# Rechargeable_battery_capacity_tester.net
KiCad netlist of a schematic drawn in EAGLE
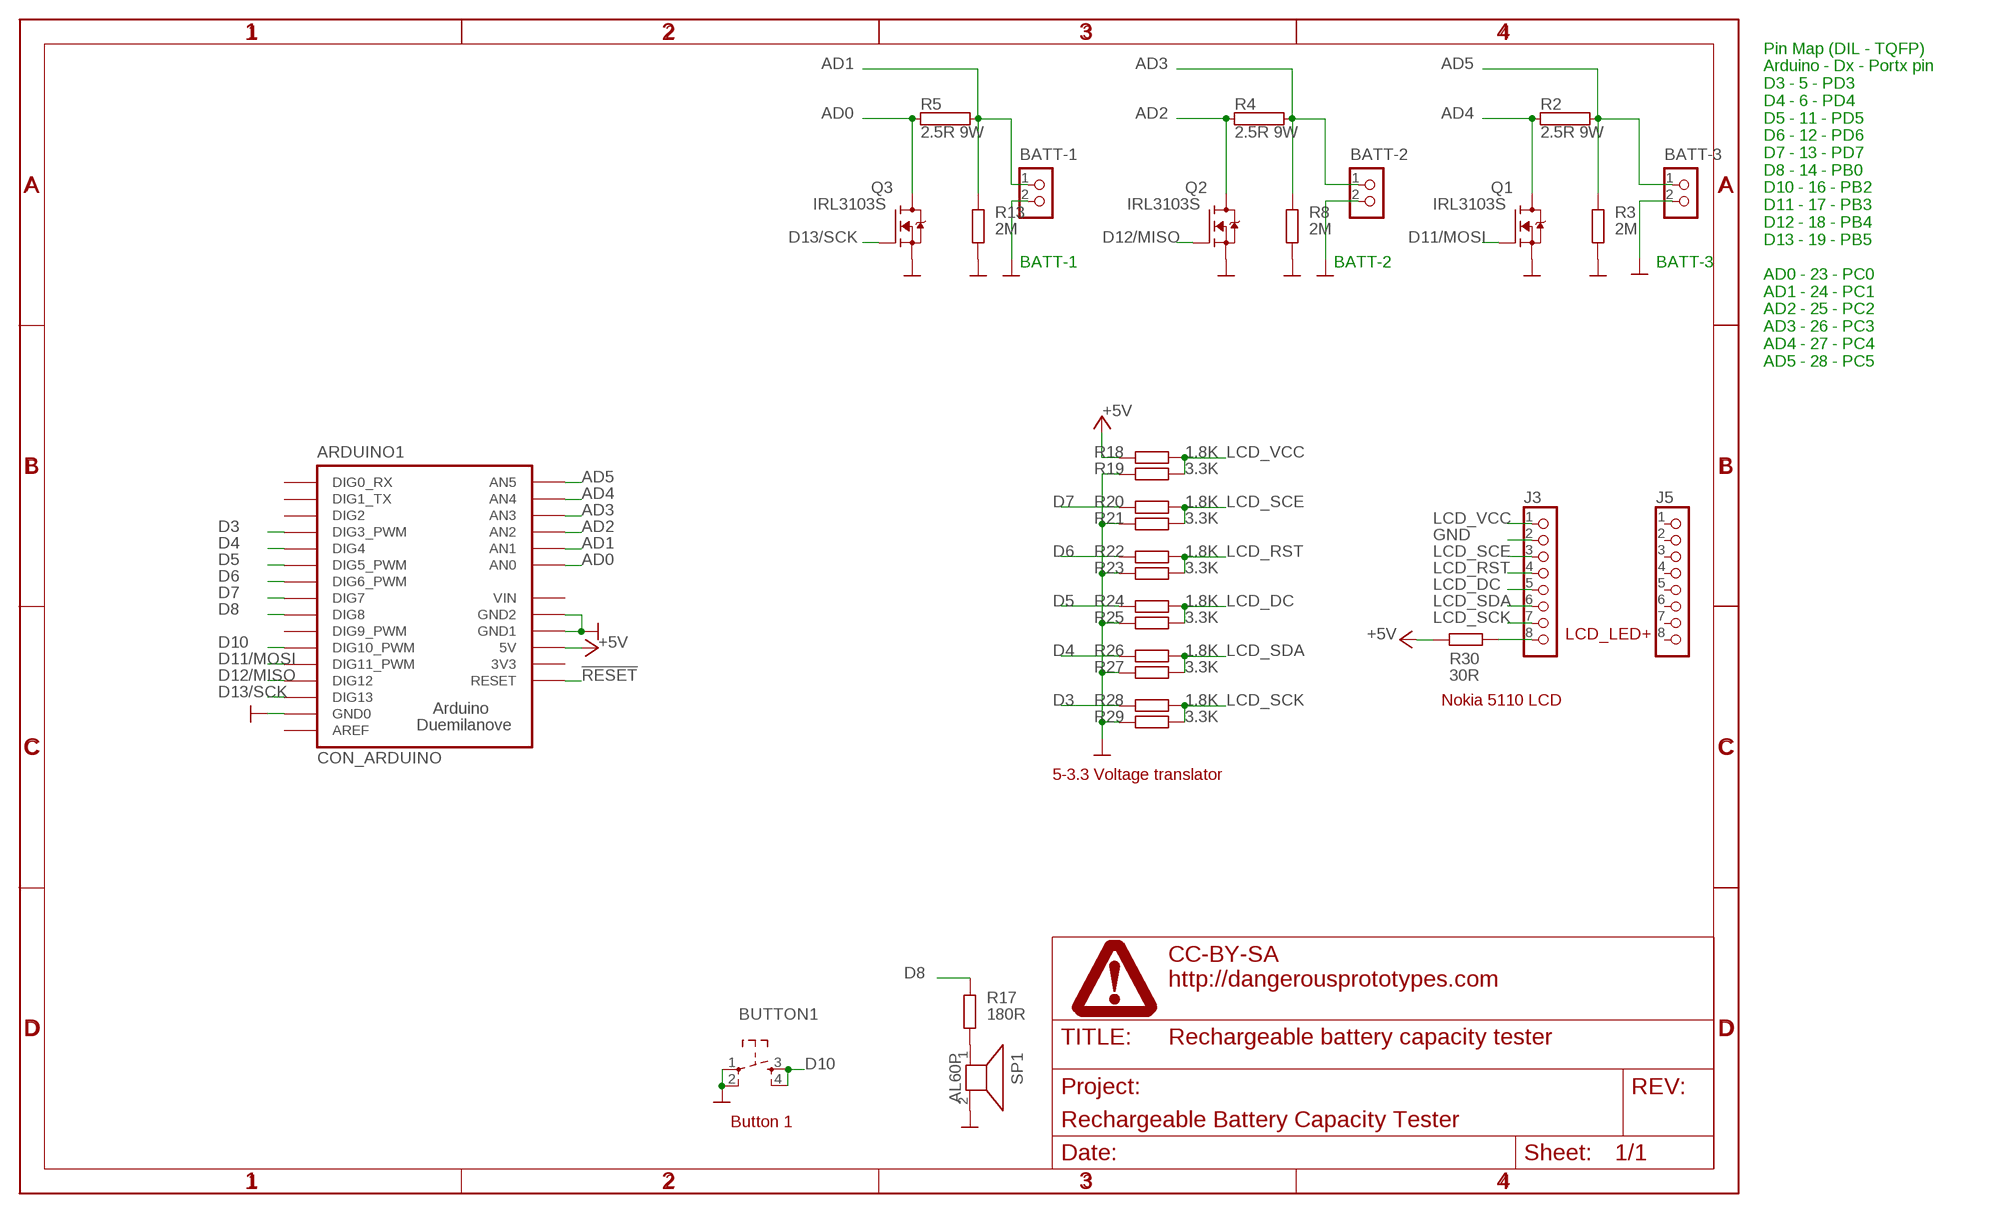
[diagram p0: schematic, sheet 1]

(export (version "E")
  (design (tool "Eeschema 10.0.6"))
  (components
    (comp (ref "ARDUINO1")
      (value "CON_ARDUINO")
      (footprint "eagle-import:CON_ARDUINO")
      (libsource (lib "eagle-import") (part "CON_ARDUINO"))
    )
    (comp (ref "BATT-1")
      (value "CON_TERMINAL_BLOCK_02-5MM")
      (footprint "eagle-import:TERMINAL_BLOCK_2P_5")
      (libsource (lib "eagle-import") (part "CON_TERMINAL_BLOCK_02-5MM"))
    )
    (comp (ref "BATT-2")
      (value "CON_TERMINAL_BLOCK_02-5MM")
      (footprint "eagle-import:TERMINAL_BLOCK_2P_5")
      (libsource (lib "eagle-import") (part "CON_TERMINAL_BLOCK_02-5MM"))
    )
    (comp (ref "BATT-3")
      (value "CON_TERMINAL_BLOCK_02-5MM")
      (footprint "eagle-import:TERMINAL_BLOCK_2P_5")
      (libsource (lib "eagle-import") (part "CON_TERMINAL_BLOCK_02-5MM"))
    )
    (comp (ref "BUTTON1")
      (value "SW_TACT_4P")
      (footprint "eagle-import:SW_TACT_SMALL")
      (libsource (lib "eagle-import") (part "SW_TACT_4P"))
    )
    (comp (ref "J3")
      (value "CON_HEADER_1X08-PTH")
      (footprint "eagle-import:M1X8")
      (libsource (lib "eagle-import") (part "CON_HEADER_1X08-PTH"))
    )
    (comp (ref "J5")
      (value "CON_HEADER_1X08-PTH")
      (footprint "eagle-import:M1X8")
      (libsource (lib "eagle-import") (part "CON_HEADER_1X08-PTH"))
    )
    (comp (ref "Q1")
      (value "IRL3103S")
      (footprint "eagle-import:D2PAK")
      (libsource (lib "eagle-import") (part "TRANSISTOR_MOSFET-N-D2PAK"))
    )
    (comp (ref "Q2")
      (value "IRL3103S")
      (footprint "eagle-import:D2PAK")
      (libsource (lib "eagle-import") (part "TRANSISTOR_MOSFET-N-D2PAK"))
    )
    (comp (ref "Q3")
      (value "IRL3103S")
      (footprint "eagle-import:D2PAK")
      (libsource (lib "eagle-import") (part "TRANSISTOR_MOSFET-N-D2PAK"))
    )
    (comp (ref "R2")
      (value "2.5R 9W")
      (footprint "eagle-import:KH208-8")
      (libsource (lib "eagle-import") (part "RKH208-8"))
    )
    (comp (ref "R3")
      (value "2M")
      (footprint "eagle-import:R603")
      (libsource (lib "eagle-import") (part "RESISTOR-0603"))
    )
    (comp (ref "R4")
      (value "2.5R 9W")
      (footprint "eagle-import:KH208-8")
      (libsource (lib "eagle-import") (part "RKH208-8"))
    )
    (comp (ref "R5")
      (value "2.5R 9W")
      (footprint "eagle-import:KH208-8")
      (libsource (lib "eagle-import") (part "RKH208-8"))
    )
    (comp (ref "R8")
      (value "2M")
      (footprint "eagle-import:R603")
      (libsource (lib "eagle-import") (part "RESISTOR-0603"))
    )
    (comp (ref "R13")
      (value "2M")
      (footprint "eagle-import:R603")
      (libsource (lib "eagle-import") (part "RESISTOR-0603"))
    )
    (comp (ref "R17")
      (value "180R")
      (footprint "eagle-import:R603")
      (libsource (lib "eagle-import") (part "RESISTOR-0603"))
    )
    (comp (ref "R18")
      (value "1.8K")
      (footprint "eagle-import:R603")
      (libsource (lib "eagle-import") (part "RESISTOR-0603"))
    )
    (comp (ref "R19")
      (value "3.3K")
      (footprint "eagle-import:R603")
      (libsource (lib "eagle-import") (part "RESISTOR-0603"))
    )
    (comp (ref "R20")
      (value "1.8K")
      (footprint "eagle-import:R603")
      (libsource (lib "eagle-import") (part "RESISTOR-0603"))
    )
    (comp (ref "R21")
      (value "3.3K")
      (footprint "eagle-import:R603")
      (libsource (lib "eagle-import") (part "RESISTOR-0603"))
    )
    (comp (ref "R22")
      (value "1.8K")
      (footprint "eagle-import:R603")
      (libsource (lib "eagle-import") (part "RESISTOR-0603"))
    )
    (comp (ref "R23")
      (value "3.3K")
      (footprint "eagle-import:R603")
      (libsource (lib "eagle-import") (part "RESISTOR-0603"))
    )
    (comp (ref "R24")
      (value "1.8K")
      (footprint "eagle-import:R603")
      (libsource (lib "eagle-import") (part "RESISTOR-0603"))
    )
    (comp (ref "R25")
      (value "3.3K")
      (footprint "eagle-import:R603")
      (libsource (lib "eagle-import") (part "RESISTOR-0603"))
    )
    (comp (ref "R26")
      (value "1.8K")
      (footprint "eagle-import:R603")
      (libsource (lib "eagle-import") (part "RESISTOR-0603"))
    )
    (comp (ref "R27")
      (value "3.3K")
      (footprint "eagle-import:R603")
      (libsource (lib "eagle-import") (part "RESISTOR-0603"))
    )
    (comp (ref "R28")
      (value "1.8K")
      (footprint "eagle-import:R603")
      (libsource (lib "eagle-import") (part "RESISTOR-0603"))
    )
    (comp (ref "R29")
      (value "3.3K")
      (footprint "eagle-import:R603")
      (libsource (lib "eagle-import") (part "RESISTOR-0603"))
    )
    (comp (ref "R30")
      (value "30R")
      (footprint "eagle-import:R603")
      (libsource (lib "eagle-import") (part "RESISTOR-0603"))
    )
    (comp (ref "SP1")
      (value "AL60P")
      (footprint "eagle-import:AL60P")
      (libsource (lib "eagle-import") (part "AL60P"))
    )
    (comp (ref "U$1")
      (value "FRAME_DINA4_L")
      (footprint "eagle-import:DP_LOGO")
      (fields
        (field (name "FF1") "Credits to: http://www.instructables.com/member/BrianH/")
        (field (name "PROJECT") "Rechargeable Battery Capacity Tester")
        (field (name "URL1") "http://dangerousprototypes.com")
        (field (name "URL2") "http://www.instructables.com/id/Rechargeable-Battery-Capacity-Tester/")
      )
      (libsource (lib "eagle-import") (part "FRAME_DINA4_L"))
    )
  )
  (nets
    (net (code "1") (name "/AD0") (class "Default")
      (node (ref "ARDUINO1") (pin "A_0") (pinfunction "AN0_A_0") (pintype "input"))
      (node (ref "Q3") (pin "2") (pinfunction "D_2") (pintype "passive"))
      (node (ref "R5") (pin "1") (pinfunction "1_1") (pintype "passive"))
    )
    (net (code "2") (name "/AD1") (class "Default")
      (node (ref "ARDUINO1") (pin "A_1") (pinfunction "AN1_A_1") (pintype "input"))
      (node (ref "BATT-1") (pin "1") (pinfunction "1_1") (pintype "passive"))
      (node (ref "R13") (pin "2") (pinfunction "2_2") (pintype "passive"))
      (node (ref "R5") (pin "2") (pinfunction "2_2") (pintype "passive"))
    )
    (net (code "3") (name "/AD2") (class "Default")
      (node (ref "ARDUINO1") (pin "A_2") (pinfunction "AN2_A_2") (pintype "input"))
      (node (ref "Q2") (pin "2") (pinfunction "D_2") (pintype "passive"))
      (node (ref "R4") (pin "1") (pinfunction "1_1") (pintype "passive"))
    )
    (net (code "4") (name "/AD3") (class "Default")
      (node (ref "ARDUINO1") (pin "A_3") (pinfunction "AN3_A_3") (pintype "input"))
      (node (ref "BATT-2") (pin "1") (pinfunction "1_1") (pintype "passive"))
      (node (ref "R4") (pin "2") (pinfunction "2_2") (pintype "passive"))
      (node (ref "R8") (pin "2") (pinfunction "2_2") (pintype "passive"))
    )
    (net (code "5") (name "/AD4") (class "Default")
      (node (ref "ARDUINO1") (pin "A_4") (pinfunction "AN4_A_4") (pintype "input"))
      (node (ref "Q1") (pin "2") (pinfunction "D_2") (pintype "passive"))
      (node (ref "R2") (pin "1") (pinfunction "1_1") (pintype "passive"))
    )
    (net (code "6") (name "/AD5") (class "Default")
      (node (ref "ARDUINO1") (pin "A_5") (pinfunction "AN5_A_5") (pintype "input"))
      (node (ref "BATT-3") (pin "1") (pinfunction "1_1") (pintype "passive"))
      (node (ref "R2") (pin "2") (pinfunction "2_2") (pintype "passive"))
      (node (ref "R3") (pin "2") (pinfunction "2_2") (pintype "passive"))
    )
    (net (code "7") (name "/D3") (class "Default")
      (node (ref "ARDUINO1") (pin "D_3") (pinfunction "DIG3_PWM_D_3") (pintype "bidirectional"))
      (node (ref "R28") (pin "1") (pinfunction "1_1") (pintype "passive"))
    )
    (net (code "8") (name "/D4") (class "Default")
      (node (ref "ARDUINO1") (pin "D_4") (pinfunction "DIG4_D_4") (pintype "bidirectional"))
      (node (ref "R26") (pin "1") (pinfunction "1_1") (pintype "passive"))
    )
    (net (code "9") (name "/D5") (class "Default")
      (node (ref "ARDUINO1") (pin "D_5") (pinfunction "DIG5_PWM_D_5") (pintype "bidirectional"))
      (node (ref "R24") (pin "1") (pinfunction "1_1") (pintype "passive"))
    )
    (net (code "10") (name "/D6") (class "Default")
      (node (ref "ARDUINO1") (pin "D_6") (pinfunction "DIG6_PWM_D_6") (pintype "bidirectional"))
      (node (ref "R22") (pin "1") (pinfunction "1_1") (pintype "passive"))
    )
    (net (code "11") (name "/D7") (class "Default")
      (node (ref "ARDUINO1") (pin "D_7") (pinfunction "DIG7_D_7") (pintype "bidirectional"))
      (node (ref "R20") (pin "1") (pinfunction "1_1") (pintype "passive"))
    )
    (net (code "12") (name "/D8") (class "Default")
      (node (ref "ARDUINO1") (pin "D_8") (pinfunction "DIG8_D_8") (pintype "bidirectional"))
      (node (ref "R17") (pin "2") (pinfunction "2_2") (pintype "passive"))
    )
    (net (code "13") (name "/D10") (class "Default")
      (node (ref "ARDUINO1") (pin "D_10") (pinfunction "DIG10_PWM_D_10") (pintype "bidirectional"))
      (node (ref "BUTTON1") (pin "3") (pinfunction "3_3") (pintype "passive"))
      (node (ref "BUTTON1") (pin "4") (pinfunction "4_4") (pintype "passive"))
    )
    (net (code "14") (name "/D11{slash}MOSI") (class "Default")
      (node (ref "ARDUINO1") (pin "D_11") (pinfunction "DIG11_PWM_D_11") (pintype "bidirectional"))
      (node (ref "Q1") (pin "1") (pinfunction "G_1") (pintype "passive"))
    )
    (net (code "15") (name "/D12{slash}MISO") (class "Default")
      (node (ref "ARDUINO1") (pin "D_12") (pinfunction "DIG12_D_12") (pintype "bidirectional"))
      (node (ref "Q2") (pin "1") (pinfunction "G_1") (pintype "passive"))
    )
    (net (code "16") (name "/D13{slash}SCK") (class "Default")
      (node (ref "ARDUINO1") (pin "D_13") (pinfunction "DIG13_D_13") (pintype "bidirectional"))
      (node (ref "Q3") (pin "1") (pinfunction "G_1") (pintype "passive"))
    )
    (net (code "17") (name "/LCD_DC") (class "Default")
      (node (ref "J3") (pin "5") (pinfunction "5_5") (pintype "passive"))
      (node (ref "R24") (pin "2") (pinfunction "2_2") (pintype "passive"))
      (node (ref "R25") (pin "2") (pinfunction "2_2") (pintype "passive"))
    )
    (net (code "18") (name "/LCD_RST") (class "Default")
      (node (ref "J3") (pin "4") (pinfunction "4_4") (pintype "passive"))
      (node (ref "R22") (pin "2") (pinfunction "2_2") (pintype "passive"))
      (node (ref "R23") (pin "2") (pinfunction "2_2") (pintype "passive"))
    )
    (net (code "19") (name "/LCD_SCE") (class "Default")
      (node (ref "J3") (pin "3") (pinfunction "3_3") (pintype "passive"))
      (node (ref "R20") (pin "2") (pinfunction "2_2") (pintype "passive"))
      (node (ref "R21") (pin "2") (pinfunction "2_2") (pintype "passive"))
    )
    (net (code "20") (name "/LCD_SCK") (class "Default")
      (node (ref "J3") (pin "7") (pinfunction "7_7") (pintype "passive"))
      (node (ref "R28") (pin "2") (pinfunction "2_2") (pintype "passive"))
      (node (ref "R29") (pin "2") (pinfunction "2_2") (pintype "passive"))
    )
    (net (code "21") (name "/LCD_SDA") (class "Default")
      (node (ref "J3") (pin "6") (pinfunction "6_6") (pintype "passive"))
      (node (ref "R26") (pin "2") (pinfunction "2_2") (pintype "passive"))
      (node (ref "R27") (pin "2") (pinfunction "2_2") (pintype "passive"))
    )
    (net (code "22") (name "/LCD_VCC") (class "Default")
      (node (ref "J3") (pin "1") (pinfunction "1_1") (pintype "passive"))
      (node (ref "R18") (pin "2") (pinfunction "2_2") (pintype "passive"))
      (node (ref "R19") (pin "2") (pinfunction "2_2") (pintype "passive"))
    )
    (net (code "23") (name "/VIN") (class "Default")
      (node (ref "ARDUINO1") (pin "VIN") (pinfunction "VIN_VIN") (pintype "power_in"))
    )
    (net (code "24") (name "/~{RESET}") (class "Default")
      (node (ref "ARDUINO1") (pin "RESET") (pinfunction "RESET_RESET") (pintype "input"))
    )
    (net (code "25") (name "Net-(J3-Pad8)") (class "Default")
      (node (ref "J3") (pin "8") (pinfunction "8_8") (pintype "passive"))
      (node (ref "R30") (pin "2") (pinfunction "2_2") (pintype "passive"))
    )
    (net (code "26") (name "Net-(R17-Pad1)") (class "Default")
      (node (ref "R17") (pin "1") (pinfunction "1_1") (pintype "passive"))
      (node (ref "SP1") (pin "1") (pinfunction "1_1") (pintype "passive"))
    )
    (net (code "27") (name "SUPPLY_+5V") (class "Default")
      (node (ref "ARDUINO1") (pin "5V") (pinfunction "5V_5V") (pintype "bidirectional"))
      (node (ref "R18") (pin "1") (pinfunction "1_1") (pintype "passive"))
      (node (ref "R30") (pin "1") (pinfunction "1_1") (pintype "passive"))
    )
    (net (code "28") (name "SUPPLY_GND") (class "Default")
      (node (ref "ARDUINO1") (pin "GND0") (pinfunction "GND0_GND0") (pintype "power_in"))
      (node (ref "ARDUINO1") (pin "GND1") (pinfunction "GND1_GND1") (pintype "power_in"))
      (node (ref "ARDUINO1") (pin "GND2") (pinfunction "GND2_GND2") (pintype "power_in"))
      (node (ref "BATT-1") (pin "2") (pinfunction "2_2") (pintype "passive"))
      (node (ref "BATT-2") (pin "2") (pinfunction "2_2") (pintype "passive"))
      (node (ref "BATT-3") (pin "2") (pinfunction "2_2") (pintype "passive"))
      (node (ref "BUTTON1") (pin "1") (pinfunction "1_1") (pintype "passive"))
      (node (ref "BUTTON1") (pin "2") (pinfunction "2_2") (pintype "passive"))
      (node (ref "J3") (pin "2") (pinfunction "2_2") (pintype "passive"))
      (node (ref "Q1") (pin "3") (pinfunction "S_3") (pintype "passive"))
      (node (ref "Q2") (pin "3") (pinfunction "S_3") (pintype "passive"))
      (node (ref "Q3") (pin "3") (pinfunction "S_3") (pintype "passive"))
      (node (ref "R13") (pin "1") (pinfunction "1_1") (pintype "passive"))
      (node (ref "R19") (pin "1") (pinfunction "1_1") (pintype "passive"))
      (node (ref "R21") (pin "1") (pinfunction "1_1") (pintype "passive"))
      (node (ref "R23") (pin "1") (pinfunction "1_1") (pintype "passive"))
      (node (ref "R25") (pin "1") (pinfunction "1_1") (pintype "passive"))
      (node (ref "R27") (pin "1") (pinfunction "1_1") (pintype "passive"))
      (node (ref "R29") (pin "1") (pinfunction "1_1") (pintype "passive"))
      (node (ref "R3") (pin "1") (pinfunction "1_1") (pintype "passive"))
      (node (ref "R8") (pin "1") (pinfunction "1_1") (pintype "passive"))
      (node (ref "SP1") (pin "2") (pinfunction "2_2") (pintype "passive"))
    )
    (net (code "29") (name "unconnected-(ARDUINO1-DIG0_RX-PadD_0)") (class "Default")
      (node (ref "ARDUINO1") (pin "D_0") (pinfunction "DIG0_RX_D_0") (pintype "bidirectional"))
    )
    (net (code "30") (name "unconnected-(ARDUINO1-DIG1_TX-PadD_1)") (class "Default")
      (node (ref "ARDUINO1") (pin "D_1") (pinfunction "DIG1_TX_D_1") (pintype "bidirectional"))
    )
    (net (code "31") (name "unconnected-(ARDUINO1-DIG2-PadD_2)") (class "Default")
      (node (ref "ARDUINO1") (pin "D_2") (pinfunction "DIG2_D_2") (pintype "bidirectional"))
    )
    (net (code "32") (name "unconnected-(ARDUINO1-DIG9_PWM-PadD_9)") (class "Default")
      (node (ref "ARDUINO1") (pin "D_9") (pinfunction "DIG9_PWM_D_9") (pintype "bidirectional"))
    )
    (net (code "33") (name "unconnected-(ARDUINO1-Pad3V3)") (class "Default")
      (node (ref "ARDUINO1") (pin "3V3") (pinfunction "3V3_3V3") (pintype "bidirectional"))
    )
    (net (code "34") (name "unconnected-(ARDUINO1-PadAREF)") (class "Default")
      (node (ref "ARDUINO1") (pin "AREF") (pinfunction "AREF_AREF") (pintype "bidirectional"))
    )
    (net (code "35") (name "unconnected-(J5-Pad1)") (class "Default")
      (node (ref "J5") (pin "1") (pinfunction "1_1") (pintype "passive"))
    )
    (net (code "36") (name "unconnected-(J5-Pad2)") (class "Default")
      (node (ref "J5") (pin "2") (pinfunction "2_2") (pintype "passive"))
    )
    (net (code "37") (name "unconnected-(J5-Pad3)") (class "Default")
      (node (ref "J5") (pin "3") (pinfunction "3_3") (pintype "passive"))
    )
    (net (code "38") (name "unconnected-(J5-Pad4)") (class "Default")
      (node (ref "J5") (pin "4") (pinfunction "4_4") (pintype "passive"))
    )
    (net (code "39") (name "unconnected-(J5-Pad5)") (class "Default")
      (node (ref "J5") (pin "5") (pinfunction "5_5") (pintype "passive"))
    )
    (net (code "40") (name "unconnected-(J5-Pad6)") (class "Default")
      (node (ref "J5") (pin "6") (pinfunction "6_6") (pintype "passive"))
    )
    (net (code "41") (name "unconnected-(J5-Pad7)") (class "Default")
      (node (ref "J5") (pin "7") (pinfunction "7_7") (pintype "passive"))
    )
    (net (code "42") (name "unconnected-(J5-Pad8)") (class "Default")
      (node (ref "J5") (pin "8") (pinfunction "8_8") (pintype "passive"))
    )
  )
)
